# Quadromotor_BoosterPack_v1.net
KiCad netlist of a schematic drawn in EAGLE
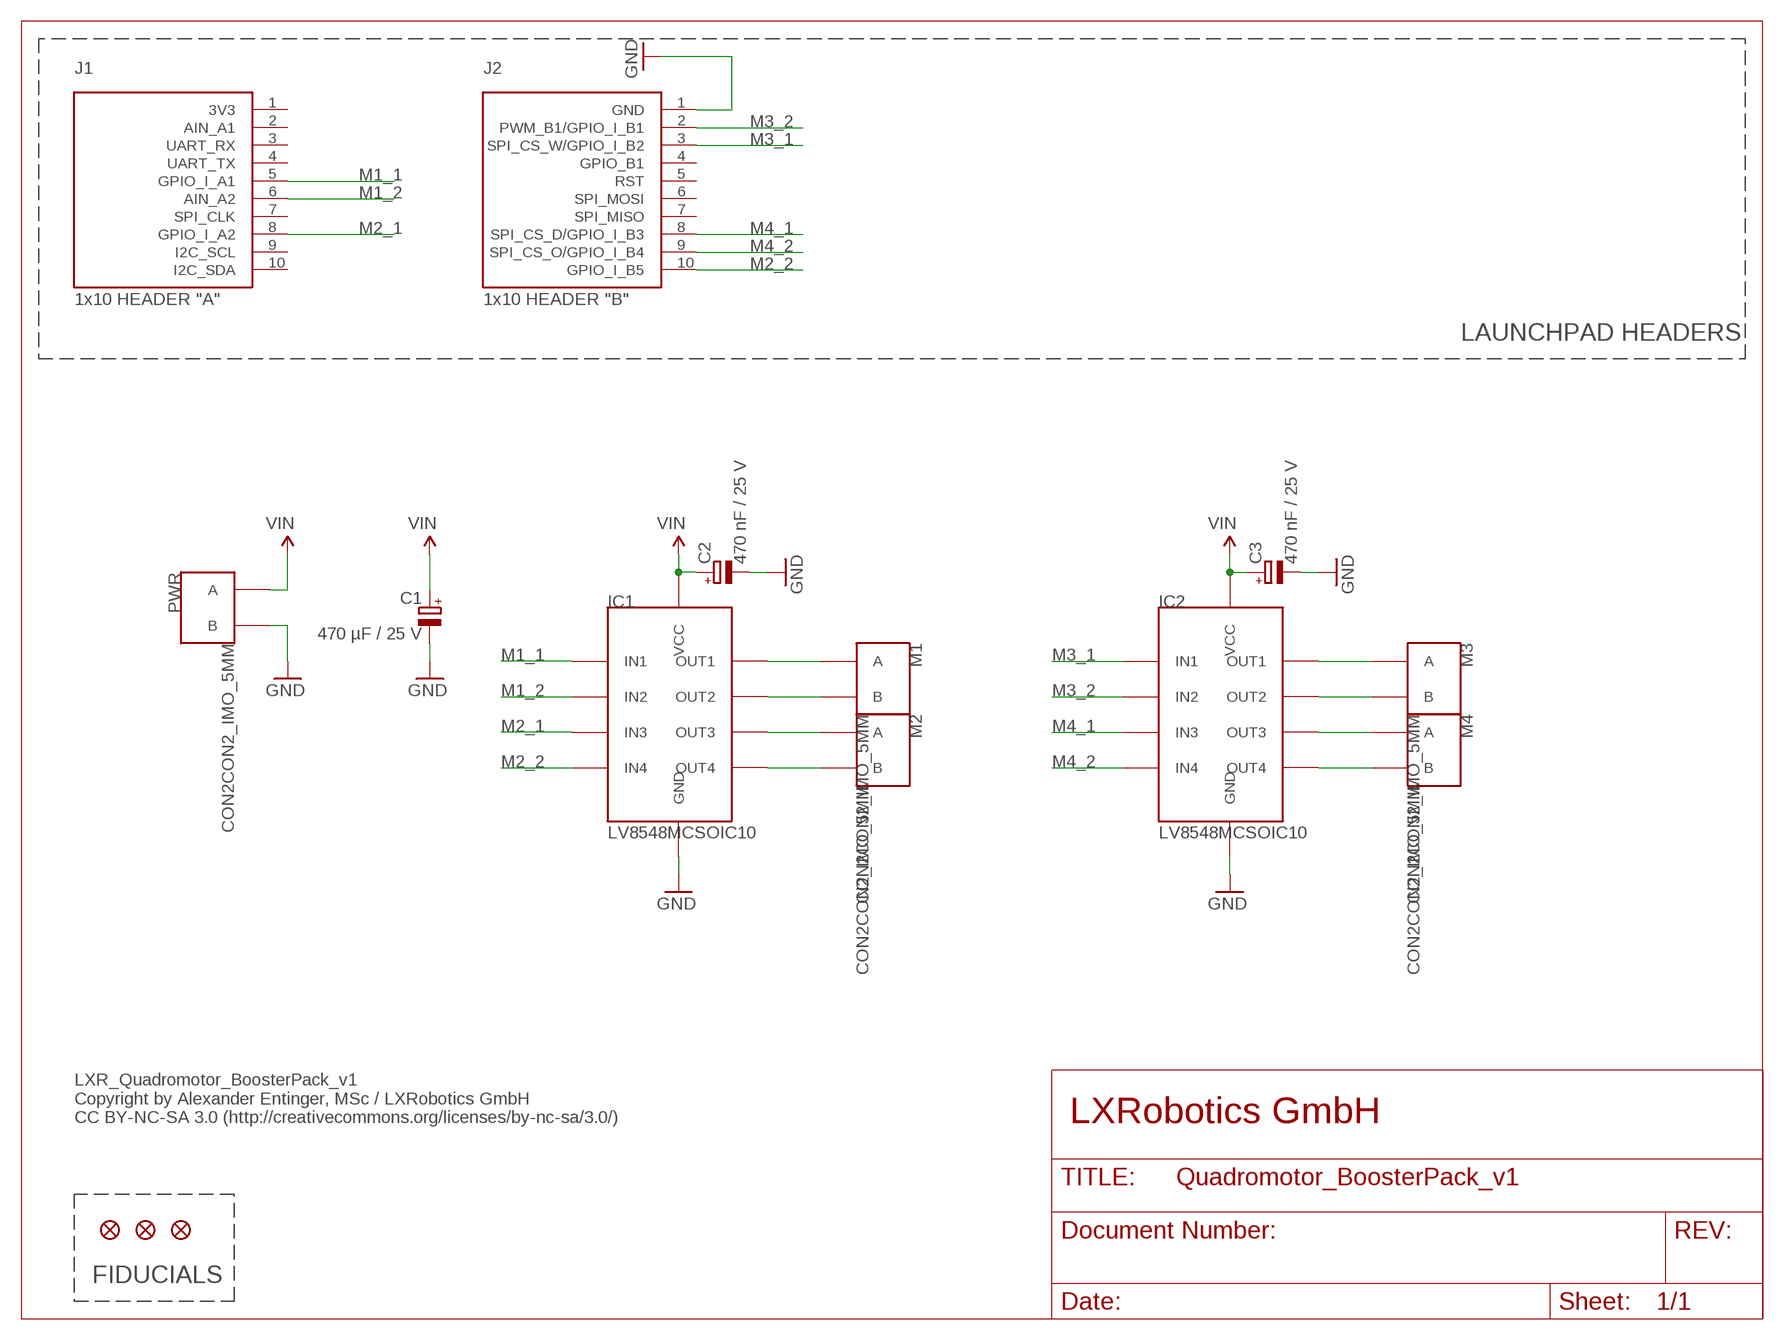
[diagram p0: schematic, sheet 1]

(export (version "E")
  (design (tool "Eeschema 10.0.6"))
  (components
    (comp (ref "C1")
      (value "470 µF / 25 V")
      (footprint "eagle-import:E5-10,5")
      (libsource (lib "eagle-import") (part "resistor_CPOL-EUE5-10.5"))
    )
    (comp (ref "C2")
      (value "470 nF / 25 V")
      (footprint "eagle-import:KEMET_A")
      (libsource (lib "eagle-import") (part "CPOL-EU"))
    )
    (comp (ref "C3")
      (value "470 nF / 25 V")
      (footprint "eagle-import:KEMET_A")
      (libsource (lib "eagle-import") (part "CPOL-EU"))
    )
    (comp (ref "FID1")
      (value "FIDUCIAL")
      (footprint "eagle-import:FIDUCIAL_L10")
      (libsource (lib "eagle-import") (part "FIDUCIAL"))
    )
    (comp (ref "FID2")
      (value "FIDUCIAL")
      (footprint "eagle-import:FIDUCIAL_L10")
      (libsource (lib "eagle-import") (part "FIDUCIAL"))
    )
    (comp (ref "FID3")
      (value "FIDUCIAL")
      (footprint "eagle-import:FIDUCIAL_L10")
      (libsource (lib "eagle-import") (part "FIDUCIAL"))
    )
    (comp (ref "IC1")
      (value "LV8548MCSOIC10")
      (footprint "eagle-import:SOIC10")
      (libsource (lib "eagle-import") (part "LV8548MCSOIC10"))
    )
    (comp (ref "IC2")
      (value "LV8548MCSOIC10")
      (footprint "eagle-import:SOIC10")
      (libsource (lib "eagle-import") (part "LV8548MCSOIC10"))
    )
    (comp (ref "J1")
      (value "1x10 HEADER \"A\"")
      (footprint "eagle-import:1X10")
      (libsource (lib "eagle-import") (part "HEADER-1X10-J1"))
    )
    (comp (ref "J2")
      (value "1x10 HEADER \"B\"")
      (footprint "eagle-import:1X10")
      (libsource (lib "eagle-import") (part "HEADER-1X10-J2"))
    )
    (comp (ref "M1")
      (value "CON2CON2_IMO_5MM")
      (footprint "eagle-import:CON2_IMO")
      (libsource (lib "eagle-import") (part "CON2CON2_IMO_5MM"))
    )
    (comp (ref "M2")
      (value "CON2CON2_IMO_5MM")
      (footprint "eagle-import:CON2_IMO")
      (libsource (lib "eagle-import") (part "CON2CON2_IMO_5MM"))
    )
    (comp (ref "M3")
      (value "CON2CON2_IMO_5MM")
      (footprint "eagle-import:CON2_IMO")
      (libsource (lib "eagle-import") (part "CON2CON2_IMO_5MM"))
    )
    (comp (ref "M4")
      (value "CON2CON2_IMO_5MM")
      (footprint "eagle-import:CON2_IMO")
      (libsource (lib "eagle-import") (part "CON2CON2_IMO_5MM"))
    )
    (comp (ref "PWR")
      (value "CON2CON2_IMO_5MM")
      (footprint "eagle-import:CON2_IMO")
      (libsource (lib "eagle-import") (part "CON2CON2_IMO_5MM"))
    )
  )
  (nets
    (net (code "1") (name "/M1_1") (class "Default")
      (node (ref "IC1") (pin "2") (pinfunction "IN1_2") (pintype "bidirectional"))
      (node (ref "J1") (pin "5") (pinfunction "GPIO_I_A1_5") (pintype "bidirectional"))
    )
    (net (code "2") (name "/M1_2") (class "Default")
      (node (ref "IC1") (pin "3") (pinfunction "IN2_3") (pintype "bidirectional"))
      (node (ref "J1") (pin "6") (pinfunction "AIN_A2_6") (pintype "bidirectional"))
    )
    (net (code "3") (name "/M2_1") (class "Default")
      (node (ref "IC1") (pin "4") (pinfunction "IN3_4") (pintype "bidirectional"))
      (node (ref "J1") (pin "8") (pinfunction "GPIO_I_A2_8") (pintype "bidirectional"))
    )
    (net (code "4") (name "/M2_2") (class "Default")
      (node (ref "IC1") (pin "5") (pinfunction "IN4_5") (pintype "bidirectional"))
      (node (ref "J2") (pin "10") (pinfunction "GPIO_I_B5_10") (pintype "bidirectional"))
    )
    (net (code "5") (name "/M3_1") (class "Default")
      (node (ref "IC2") (pin "2") (pinfunction "IN1_2") (pintype "bidirectional"))
      (node (ref "J2") (pin "3") (pinfunction "SPI_CS_W/GPIO_I_B2_3") (pintype "bidirectional"))
    )
    (net (code "6") (name "/M3_2") (class "Default")
      (node (ref "IC2") (pin "3") (pinfunction "IN2_3") (pintype "bidirectional"))
      (node (ref "J2") (pin "2") (pinfunction "PWM_B1/GPIO_I_B1_2") (pintype "bidirectional"))
    )
    (net (code "7") (name "/M4_1") (class "Default")
      (node (ref "IC2") (pin "4") (pinfunction "IN3_4") (pintype "bidirectional"))
      (node (ref "J2") (pin "8") (pinfunction "SPI_CS_D/GPIO_I_B3_8") (pintype "bidirectional"))
    )
    (net (code "8") (name "/M4_2") (class "Default")
      (node (ref "IC2") (pin "5") (pinfunction "IN4_5") (pintype "bidirectional"))
      (node (ref "J2") (pin "9") (pinfunction "SPI_CS_O/GPIO_I_B4_9") (pintype "bidirectional"))
    )
    (net (code "9") (name "GND") (class "Default")
      (node (ref "C1") (pin "-") (pinfunction "-_-") (pintype "passive"))
      (node (ref "C2") (pin "CATHODE") (pinfunction "-_CATHODE") (pintype "passive"))
      (node (ref "C3") (pin "CATHODE") (pinfunction "-_CATHODE") (pintype "passive"))
      (node (ref "IC1") (pin "6") (pinfunction "GND_6") (pintype "bidirectional"))
      (node (ref "IC2") (pin "6") (pinfunction "GND_6") (pintype "bidirectional"))
      (node (ref "J2") (pin "1") (pinfunction "GND_1") (pintype "bidirectional"))
      (node (ref "PWR") (pin "P$2") (pinfunction "B_P$2") (pintype "bidirectional"))
    )
    (net (code "10") (name "Net-(IC1-OUT1)") (class "Default")
      (node (ref "IC1") (pin "10") (pinfunction "OUT1_10") (pintype "bidirectional"))
      (node (ref "M1") (pin "P$1") (pinfunction "A_P$1") (pintype "bidirectional"))
    )
    (net (code "11") (name "Net-(IC1-OUT2)") (class "Default")
      (node (ref "IC1") (pin "9") (pinfunction "OUT2_9") (pintype "bidirectional"))
      (node (ref "M1") (pin "P$2") (pinfunction "B_P$2") (pintype "bidirectional"))
    )
    (net (code "12") (name "Net-(IC1-OUT3)") (class "Default")
      (node (ref "IC1") (pin "8") (pinfunction "OUT3_8") (pintype "bidirectional"))
      (node (ref "M2") (pin "P$1") (pinfunction "A_P$1") (pintype "bidirectional"))
    )
    (net (code "13") (name "Net-(IC1-OUT4)") (class "Default")
      (node (ref "IC1") (pin "7") (pinfunction "OUT4_7") (pintype "bidirectional"))
      (node (ref "M2") (pin "P$2") (pinfunction "B_P$2") (pintype "bidirectional"))
    )
    (net (code "14") (name "Net-(IC2-OUT1)") (class "Default")
      (node (ref "IC2") (pin "10") (pinfunction "OUT1_10") (pintype "bidirectional"))
      (node (ref "M3") (pin "P$1") (pinfunction "A_P$1") (pintype "bidirectional"))
    )
    (net (code "15") (name "Net-(IC2-OUT2)") (class "Default")
      (node (ref "IC2") (pin "9") (pinfunction "OUT2_9") (pintype "bidirectional"))
      (node (ref "M3") (pin "P$2") (pinfunction "B_P$2") (pintype "bidirectional"))
    )
    (net (code "16") (name "Net-(IC2-OUT3)") (class "Default")
      (node (ref "IC2") (pin "8") (pinfunction "OUT3_8") (pintype "bidirectional"))
      (node (ref "M4") (pin "P$1") (pinfunction "A_P$1") (pintype "bidirectional"))
    )
    (net (code "17") (name "Net-(IC2-OUT4)") (class "Default")
      (node (ref "IC2") (pin "7") (pinfunction "OUT4_7") (pintype "bidirectional"))
      (node (ref "M4") (pin "P$2") (pinfunction "B_P$2") (pintype "bidirectional"))
    )
    (net (code "18") (name "VIN") (class "Default")
      (node (ref "C1") (pin "+") (pinfunction "+_+") (pintype "passive"))
      (node (ref "C2") (pin "ANODE") (pinfunction "+_ANODE") (pintype "passive"))
      (node (ref "C3") (pin "ANODE") (pinfunction "+_ANODE") (pintype "passive"))
      (node (ref "IC1") (pin "1") (pinfunction "VCC_1") (pintype "bidirectional"))
      (node (ref "IC2") (pin "1") (pinfunction "VCC_1") (pintype "bidirectional"))
      (node (ref "PWR") (pin "P$1") (pinfunction "A_P$1") (pintype "bidirectional"))
    )
    (net (code "19") (name "unconnected-(J1-3V3-Pad1)") (class "Default")
      (node (ref "J1") (pin "1") (pinfunction "3V3_1") (pintype "bidirectional"))
    )
    (net (code "20") (name "unconnected-(J1-AIN_A1-Pad2)") (class "Default")
      (node (ref "J1") (pin "2") (pinfunction "AIN_A1_2") (pintype "bidirectional"))
    )
    (net (code "21") (name "unconnected-(J1-I2C_SCL-Pad9)") (class "Default")
      (node (ref "J1") (pin "9") (pinfunction "I2C_SCL_9") (pintype "bidirectional"))
    )
    (net (code "22") (name "unconnected-(J1-I2C_SDA-Pad10)") (class "Default")
      (node (ref "J1") (pin "10") (pinfunction "I2C_SDA_10") (pintype "bidirectional"))
    )
    (net (code "23") (name "unconnected-(J1-SPI_CLK-Pad7)") (class "Default")
      (node (ref "J1") (pin "7") (pinfunction "SPI_CLK_7") (pintype "bidirectional"))
    )
    (net (code "24") (name "unconnected-(J1-UART_RX-Pad3)") (class "Default")
      (node (ref "J1") (pin "3") (pinfunction "UART_RX_3") (pintype "bidirectional"))
    )
    (net (code "25") (name "unconnected-(J1-UART_TX-Pad4)") (class "Default")
      (node (ref "J1") (pin "4") (pinfunction "UART_TX_4") (pintype "bidirectional"))
    )
    (net (code "26") (name "unconnected-(J2-GPIO_B1-Pad4)") (class "Default")
      (node (ref "J2") (pin "4") (pinfunction "GPIO_B1_4") (pintype "bidirectional"))
    )
    (net (code "27") (name "unconnected-(J2-RST-Pad5)") (class "Default")
      (node (ref "J2") (pin "5") (pinfunction "RST_5") (pintype "bidirectional"))
    )
    (net (code "28") (name "unconnected-(J2-SPI_MISO-Pad7)") (class "Default")
      (node (ref "J2") (pin "7") (pinfunction "SPI_MISO_7") (pintype "bidirectional"))
    )
    (net (code "29") (name "unconnected-(J2-SPI_MOSI-Pad6)") (class "Default")
      (node (ref "J2") (pin "6") (pinfunction "SPI_MOSI_6") (pintype "bidirectional"))
    )
  )
)
